# MP-Mosaic.net
KiCad netlist of a schematic drawn in Altium Designer
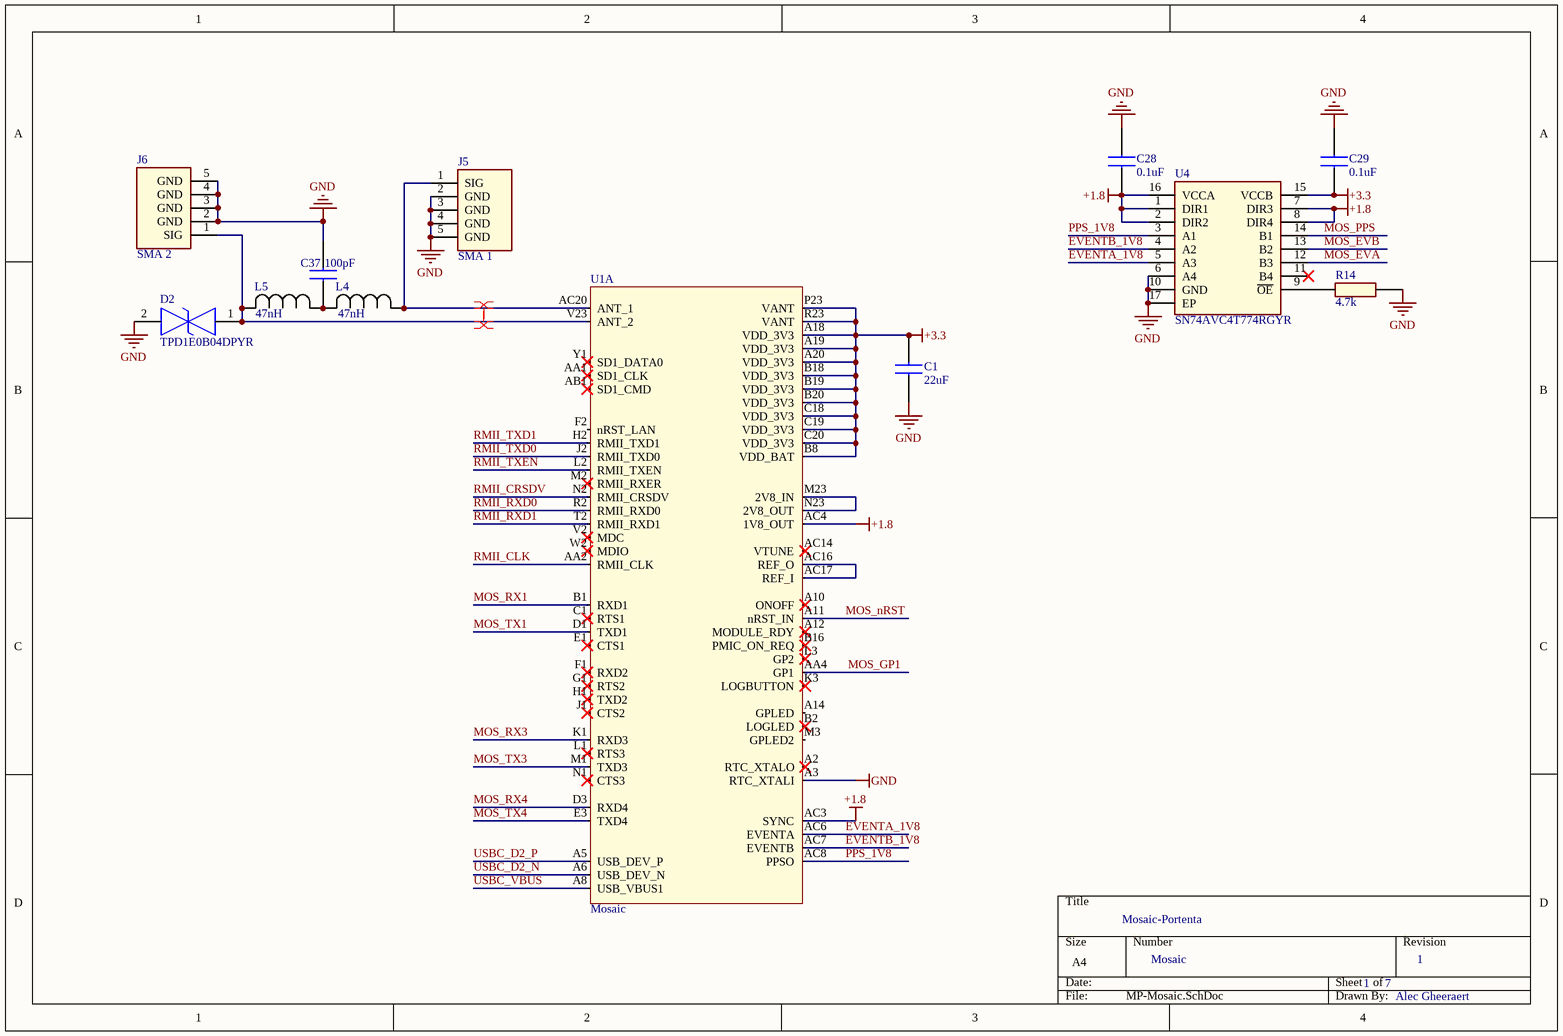
[diagram p0: MP-Mosaic.SchDoc]

(export (version "E")
  (design (tool "Eeschema 10.0.6"))
  (components
    (comp (ref "C1")
      (value "22uF")
      (footprint "CAPC2012X145N")
      (description "0805 22µF")
      (fields (field (name "MANUFACTURER") "Walsin") (field (name "TOLERANCE") "10%"))
      (libsource (lib "Ghrt") (part "0805X226K6R3CT"))
    )
    (comp (ref "C28")
      (value "0.1uF")
      (footprint "CAPC1005X55N")
      (description "0402I 0.1µF")
      (fields (field (name "MANUFACTURER") "Walsin") (field (name "TOLERANCE") "10%"))
      (libsource (lib "Ghrt") (part "MG15B104K100CT"))
    )
    (comp (ref "C29")
      (value "0.1uF")
      (footprint "CAPC1005X55N")
      (description "0402I 0.1µF")
      (fields (field (name "MANUFACTURER") "Walsin") (field (name "TOLERANCE") "10%"))
      (libsource (lib "Ghrt") (part "MG15B104K100CT"))
    )
    (comp (ref "C37")
      (value "100pF")
      (footprint "CAPC0603X35N")
      (description "0201 100pF")
      (libsource (lib "Ghrt") (part "0201N101J250CT"))
    )
    (comp (ref "D2")
      (value "TPD1E0B04DPYR")
      (footprint "TPD1E0B04DPYR")
      (description "1 Channel TVS Diode")
      (libsource (lib "Ghrt") (part "TPD1E0B04DPYR"))
    )
    (comp (ref "J5")
      (value "SMA 1")
      (footprint "3-1478978-1")
      (description "RF SMA Connector")
      (libsource (lib "") (part "3-1478978-1_1"))
    )
    (comp (ref "J6")
      (value "SMA 2")
      (footprint "3-1478978-1")
      (description "RF SMA Connector")
      (libsource (lib "Ghrt") (part "3-1478978-1"))
    )
    (comp (ref "L4")
      (value "47nH")
      (footprint "IND_1005_TDK")
      (description "47nH 1.4GHz Inductor")
      (libsource (lib "Ghrt") (part "MLG1005S47NJTD25"))
    )
    (comp (ref "L5")
      (value "47nH")
      (footprint "IND_1005_TDK")
      (description "47nH 1.4GHz Inductor")
      (libsource (lib "Ghrt") (part "MLG1005S47NJTD25"))
    )
    (comp (ref "R14")
      (value "4.7k")
      (footprint "RESC1005X40N")
      (description "0402I 4.7k")
      (fields (field (name "MANUFACTURER") "Walsin") (field (name "TOLERANCE") "1%"))
      (libsource (lib "Ghrt") (part "WR04X4701FTL"))
    )
    (comp (ref "U1")
      (value "Mosaic")
      (footprint "Mosaic")
      (description "GNSS RTK Receiver")
      (fields (field (name "MANUFACTURER") "Septentrio"))
      (libsource (lib "Ghrt") (part "CMP-00013-3"))
    )
    (comp (ref "U4")
      (value "SN74AVC4T774RGYR")
      (footprint "SN74AVC4T774RGYR")
      (description "4B Dual-Supply Level Shifter")
      (fields (field (name "MANUFACTURER") "Texas Instruments"))
      (libsource (lib "Ghrt") (part "SN74AVC4T774RGYR"))
    )
  )
  (nets
    (net (code "1") (name "+1.8") (class "Default")
      (node (ref "C28") (pin "1") (pinfunction "1_1") (pintype "passive"))
      (node (ref "U1") (pin "AC3") (pinfunction "SYNC_AC3") (pintype "input"))
      (node (ref "U1") (pin "AC4") (pinfunction "1V8_OUT_AC4") (pintype "power_in"))
      (node (ref "U4") (pin "1") (pinfunction "DIR1_1") (pintype "passive"))
      (node (ref "U4") (pin "16") (pinfunction "VCCA_16") (pintype "passive"))
      (node (ref "U4") (pin "2") (pinfunction "DIR2_2") (pintype "passive"))
      (node (ref "U4") (pin "7") (pinfunction "DIR3_7") (pintype "passive"))
      (node (ref "U4") (pin "8") (pinfunction "DIR4_8") (pintype "passive"))
    )
    (net (code "2") (name "+3.3") (class "Default")
      (node (ref "C1") (pin "1") (pinfunction "1_1") (pintype "passive"))
      (node (ref "C29") (pin "1") (pinfunction "1_1") (pintype "passive"))
      (node (ref "U1") (pin "A18") (pinfunction "VDD_3V3_A18") (pintype "power_in"))
      (node (ref "U1") (pin "A19") (pinfunction "VDD_3V3_A19") (pintype "power_in"))
      (node (ref "U1") (pin "A20") (pinfunction "VDD_3V3_A20") (pintype "power_in"))
      (node (ref "U1") (pin "B18") (pinfunction "VDD_3V3_B18") (pintype "power_in"))
      (node (ref "U1") (pin "B19") (pinfunction "VDD_3V3_B19") (pintype "power_in"))
      (node (ref "U1") (pin "B20") (pinfunction "VDD_3V3_B20") (pintype "power_in"))
      (node (ref "U1") (pin "B8") (pinfunction "VDD_BAT_B8") (pintype "power_in"))
      (node (ref "U1") (pin "C18") (pinfunction "VDD_3V3_C18") (pintype "power_in"))
      (node (ref "U1") (pin "C19") (pinfunction "VDD_3V3_C19") (pintype "power_in"))
      (node (ref "U1") (pin "C20") (pinfunction "VDD_3V3_C20") (pintype "power_in"))
      (node (ref "U1") (pin "P23") (pinfunction "VANT_P23") (pintype "power_in"))
      (node (ref "U1") (pin "R23") (pinfunction "VANT_R23") (pintype "power_in"))
      (node (ref "U4") (pin "15") (pinfunction "VCCB_15") (pintype "passive"))
    )
    (net (code "3") (name "/EVENTA_1V8") (class "Default")
      (node (ref "U1") (pin "AC6") (pinfunction "EVENTA_AC6") (pintype "input"))
      (node (ref "U4") (pin "5") (pinfunction "A3_5") (pintype "passive"))
    )
    (net (code "4") (name "/EVENTB_1V8") (class "Default")
      (node (ref "U1") (pin "AC7") (pinfunction "EVENTB_AC7") (pintype "input"))
      (node (ref "U4") (pin "4") (pinfunction "A2_4") (pintype "passive"))
    )
    (net (code "5") (name "/MOS_EVA") (class "Default")
      (node (ref "U4") (pin "12") (pinfunction "B3_12") (pintype "passive"))
    )
    (net (code "6") (name "/MOS_EVB") (class "Default")
      (node (ref "U4") (pin "13") (pinfunction "B2_13") (pintype "passive"))
    )
    (net (code "7") (name "/MOS_GP1") (class "Default")
      (node (ref "U1") (pin "AA4") (pinfunction "GP1_AA4") (pintype "output"))
    )
    (net (code "8") (name "/MOS_PPS") (class "Default")
      (node (ref "U4") (pin "14") (pinfunction "B1_14") (pintype "passive"))
    )
    (net (code "9") (name "/MOS_RX1") (class "Default")
      (node (ref "U1") (pin "B1") (pinfunction "RXD1_B1") (pintype "input"))
    )
    (net (code "10") (name "/MOS_RX3") (class "Default")
      (node (ref "U1") (pin "K1") (pinfunction "RXD3_K1") (pintype "input"))
    )
    (net (code "11") (name "/MOS_RX4") (class "Default")
      (node (ref "U1") (pin "D3") (pinfunction "RXD4_D3") (pintype "input"))
    )
    (net (code "12") (name "/MOS_TX1") (class "Default")
      (node (ref "U1") (pin "D1") (pinfunction "TXD1_D1") (pintype "output"))
    )
    (net (code "13") (name "/MOS_TX3") (class "Default")
      (node (ref "U1") (pin "M1") (pinfunction "TXD3_M1") (pintype "output"))
    )
    (net (code "14") (name "/MOS_TX4") (class "Default")
      (node (ref "U1") (pin "E3") (pinfunction "TXD4_E3") (pintype "output"))
    )
    (net (code "15") (name "/MOS_nRST") (class "Default")
      (node (ref "U1") (pin "A11") (pinfunction "nRST_IN_A11") (pintype "input"))
    )
    (net (code "16") (name "/PPS_1V8") (class "Default")
      (node (ref "U1") (pin "AC8") (pinfunction "PPSO_AC8") (pintype "output"))
      (node (ref "U4") (pin "3") (pinfunction "A1_3") (pintype "passive"))
    )
    (net (code "17") (name "/RMII_CLK") (class "Default")
      (node (ref "U1") (pin "AA2") (pinfunction "RMII_CLK_AA2") (pintype "output"))
    )
    (net (code "18") (name "/RMII_CRSDV") (class "Default")
      (node (ref "U1") (pin "N2") (pinfunction "RMII_CRSDV_N2") (pintype "input"))
    )
    (net (code "19") (name "/RMII_RXD0") (class "Default")
      (node (ref "U1") (pin "R2") (pinfunction "RMII_RXD0_R2") (pintype "input"))
    )
    (net (code "20") (name "/RMII_RXD1") (class "Default")
      (node (ref "U1") (pin "T2") (pinfunction "RMII_RXD1_T2") (pintype "input"))
    )
    (net (code "21") (name "/RMII_TXD0") (class "Default")
      (node (ref "U1") (pin "J2") (pinfunction "RMII_TXD0_J2") (pintype "output"))
    )
    (net (code "22") (name "/RMII_TXD1") (class "Default")
      (node (ref "U1") (pin "H2") (pinfunction "RMII_TXD1_H2") (pintype "output"))
    )
    (net (code "23") (name "/RMII_TXEN") (class "Default")
      (node (ref "U1") (pin "L2") (pinfunction "RMII_TXEN_L2") (pintype "output"))
    )
    (net (code "24") (name "/USBC_D2_N") (class "Default")
      (node (ref "U1") (pin "A6") (pinfunction "USB_DEV_N_A6") (pintype "bidirectional"))
    )
    (net (code "25") (name "/USBC_D2_P") (class "Default")
      (node (ref "U1") (pin "A5") (pinfunction "USB_DEV_P_A5") (pintype "bidirectional"))
    )
    (net (code "26") (name "/USBC_VBUS") (class "Default")
      (node (ref "U1") (pin "A8") (pinfunction "USB_VBUS1_A8") (pintype "power_in"))
    )
    (net (code "27") (name "GND") (class "Default")
      (node (ref "C1") (pin "2") (pinfunction "2_2") (pintype "passive"))
      (node (ref "C28") (pin "2") (pinfunction "2_2") (pintype "passive"))
      (node (ref "C29") (pin "2") (pinfunction "2_2") (pintype "passive"))
      (node (ref "C37") (pin "2") (pinfunction "2_2") (pintype "passive"))
      (node (ref "D2") (pin "2") (pinfunction "2_2") (pintype "passive"))
      (node (ref "J5") (pin "2") (pinfunction "GND_2") (pintype "passive"))
      (node (ref "J5") (pin "3") (pinfunction "GND_3") (pintype "passive"))
      (node (ref "J5") (pin "4") (pinfunction "GND_4") (pintype "passive"))
      (node (ref "J5") (pin "5") (pinfunction "GND_5") (pintype "passive"))
      (node (ref "J6") (pin "2") (pinfunction "GND_2") (pintype "passive"))
      (node (ref "J6") (pin "3") (pinfunction "GND_3") (pintype "passive"))
      (node (ref "J6") (pin "4") (pinfunction "GND_4") (pintype "passive"))
      (node (ref "J6") (pin "5") (pinfunction "GND_5") (pintype "passive"))
      (node (ref "R14") (pin "2") (pinfunction "2_2") (pintype "passive"))
      (node (ref "U1") (pin "A3") (pinfunction "RTC_XTALI_A3") (pintype "input"))
      (node (ref "U4") (pin "10") (pinfunction "GND_10") (pintype "passive"))
      (node (ref "U4") (pin "17") (pinfunction "EP_17") (pintype "passive"))
      (node (ref "U4") (pin "6") (pinfunction "A4_6") (pintype "passive"))
    )
    (net (code "28") (name "Net-(C37-Pad1)") (class "Default")
      (node (ref "C37") (pin "1") (pinfunction "1_1") (pintype "passive"))
      (node (ref "L4") (pin "2") (pinfunction "2_2") (pintype "passive"))
      (node (ref "L5") (pin "1") (pinfunction "1_1") (pintype "passive"))
    )
    (net (code "29") (name "Net-(J5-SIG)") (class "Default")
      (node (ref "J5") (pin "1") (pinfunction "SIG_1") (pintype "passive"))
      (node (ref "L4") (pin "1") (pinfunction "1_1") (pintype "passive"))
      (node (ref "U1") (pin "AC20") (pinfunction "ANT_1_AC20") (pintype "input"))
    )
    (net (code "30") (name "Net-(J6-SIG)") (class "Default")
      (node (ref "D2") (pin "1") (pinfunction "1_1") (pintype "passive"))
      (node (ref "J6") (pin "1") (pinfunction "SIG_1") (pintype "passive"))
      (node (ref "L5") (pin "2") (pinfunction "2_2") (pintype "passive"))
      (node (ref "U1") (pin "V23") (pinfunction "ANT_2_V23") (pintype "input"))
    )
    (net (code "31") (name "Net-(U1A-2V8_IN)") (class "Default")
      (node (ref "U1") (pin "M23") (pinfunction "2V8_IN_M23") (pintype "power_in"))
      (node (ref "U1") (pin "N23") (pinfunction "2V8_OUT_N23") (pintype "power_in"))
    )
    (net (code "32") (name "Net-(U1A-REF_I)") (class "Default")
      (node (ref "U1") (pin "AC16") (pinfunction "REF_O_AC16") (pintype "output"))
      (node (ref "U1") (pin "AC17") (pinfunction "REF_I_AC17") (pintype "input"))
    )
    (net (code "33") (name "Net-(U4-~{OE})") (class "Default")
      (node (ref "R14") (pin "1") (pinfunction "1_1") (pintype "passive"))
      (node (ref "U4") (pin "9") (pinfunction "~{OE}_9") (pintype "passive"))
    )
    (net (code "34") (name "unconnected-(U1A-CTS1-PadE1)") (class "Default")
      (node (ref "U1") (pin "E1") (pinfunction "CTS1_E1") (pintype "input+no_connect"))
    )
    (net (code "35") (name "unconnected-(U1A-CTS2-PadJ1)") (class "Default")
      (node (ref "U1") (pin "J1") (pinfunction "CTS2_J1") (pintype "input+no_connect"))
    )
    (net (code "36") (name "unconnected-(U1A-CTS3-PadN1)") (class "Default")
      (node (ref "U1") (pin "N1") (pinfunction "CTS3_N1") (pintype "input+no_connect"))
    )
    (net (code "37") (name "unconnected-(U1A-GP2-PadL3)") (class "Default")
      (node (ref "U1") (pin "L3") (pinfunction "GP2_L3") (pintype "output+no_connect"))
    )
    (net (code "38") (name "unconnected-(U1A-GPLED-PadA14)") (class "Default")
      (node (ref "U1") (pin "A14") (pinfunction "GPLED_A14") (pintype "output"))
    )
    (net (code "39") (name "unconnected-(U1A-GPLED2-PadM3)") (class "Default")
      (node (ref "U1") (pin "M3") (pinfunction "GPLED2_M3") (pintype "output"))
    )
    (net (code "40") (name "unconnected-(U1A-LOGBUTTON-PadK3)") (class "Default")
      (node (ref "U1") (pin "K3") (pinfunction "LOGBUTTON_K3") (pintype "input+no_connect"))
    )
    (net (code "41") (name "unconnected-(U1A-LOGLED-PadB2)") (class "Default")
      (node (ref "U1") (pin "B2") (pinfunction "LOGLED_B2") (pintype "output+no_connect"))
    )
    (net (code "42") (name "unconnected-(U1A-MDC-PadV2)") (class "Default")
      (node (ref "U1") (pin "V2") (pinfunction "MDC_V2") (pintype "output+no_connect"))
    )
    (net (code "43") (name "unconnected-(U1A-MDIO-PadW2)") (class "Default")
      (node (ref "U1") (pin "W2") (pinfunction "MDIO_W2") (pintype "bidirectional+no_connect"))
    )
    (net (code "44") (name "unconnected-(U1A-MODULE_RDY-PadA12)") (class "Default")
      (node (ref "U1") (pin "A12") (pinfunction "MODULE_RDY_A12") (pintype "output+no_connect"))
    )
    (net (code "45") (name "unconnected-(U1A-ONOFF-PadA10)") (class "Default")
      (node (ref "U1") (pin "A10") (pinfunction "ONOFF_A10") (pintype "input+no_connect"))
    )
    (net (code "46") (name "unconnected-(U1A-PMIC_ON_REQ-PadB16)") (class "Default")
      (node (ref "U1") (pin "B16") (pinfunction "PMIC_ON_REQ_B16") (pintype "output+no_connect"))
    )
    (net (code "47") (name "unconnected-(U1A-RMII_RXER-PadM2)") (class "Default")
      (node (ref "U1") (pin "M2") (pinfunction "RMII_RXER_M2") (pintype "input+no_connect"))
    )
    (net (code "48") (name "unconnected-(U1A-RTC_XTALO-PadA2)") (class "Default")
      (node (ref "U1") (pin "A2") (pinfunction "RTC_XTALO_A2") (pintype "output+no_connect"))
    )
    (net (code "49") (name "unconnected-(U1A-RTS1-PadC1)") (class "Default")
      (node (ref "U1") (pin "C1") (pinfunction "RTS1_C1") (pintype "output+no_connect"))
    )
    (net (code "50") (name "unconnected-(U1A-RTS2-PadG1)") (class "Default")
      (node (ref "U1") (pin "G1") (pinfunction "RTS2_G1") (pintype "output+no_connect"))
    )
    (net (code "51") (name "unconnected-(U1A-RTS3-PadL1)") (class "Default")
      (node (ref "U1") (pin "L1") (pinfunction "RTS3_L1") (pintype "output+no_connect"))
    )
    (net (code "52") (name "unconnected-(U1A-RXD2-PadF1)") (class "Default")
      (node (ref "U1") (pin "F1") (pinfunction "RXD2_F1") (pintype "input+no_connect"))
    )
    (net (code "53") (name "unconnected-(U1A-SD1_CLK-PadAA1)") (class "Default")
      (node (ref "U1") (pin "AA1") (pinfunction "SD1_CLK_AA1") (pintype "output+no_connect"))
    )
    (net (code "54") (name "unconnected-(U1A-SD1_CMD-PadAB1)") (class "Default")
      (node (ref "U1") (pin "AB1") (pinfunction "SD1_CMD_AB1") (pintype "output+no_connect"))
    )
    (net (code "55") (name "unconnected-(U1A-SD1_DATA0-PadY1)") (class "Default")
      (node (ref "U1") (pin "Y1") (pinfunction "SD1_DATA0_Y1") (pintype "bidirectional+no_connect"))
    )
    (net (code "56") (name "unconnected-(U1A-TXD2-PadH1)") (class "Default")
      (node (ref "U1") (pin "H1") (pinfunction "TXD2_H1") (pintype "output+no_connect"))
    )
    (net (code "57") (name "unconnected-(U1A-VTUNE-PadAC14)") (class "Default")
      (node (ref "U1") (pin "AC14") (pinfunction "VTUNE_AC14") (pintype "input+no_connect"))
    )
    (net (code "58") (name "unconnected-(U1A-nRST_LAN-PadF2)") (class "Default")
      (node (ref "U1") (pin "F2") (pinfunction "nRST_LAN_F2") (pintype "output"))
    )
    (net (code "59") (name "unconnected-(U4-B4-Pad11)") (class "Default")
      (node (ref "U4") (pin "11") (pinfunction "B4_11") (pintype "passive+no_connect"))
    )
  )
)
